# SCH_card_2024-05-29.net
KiCad netlist of a schematic drawn in EasyEDA
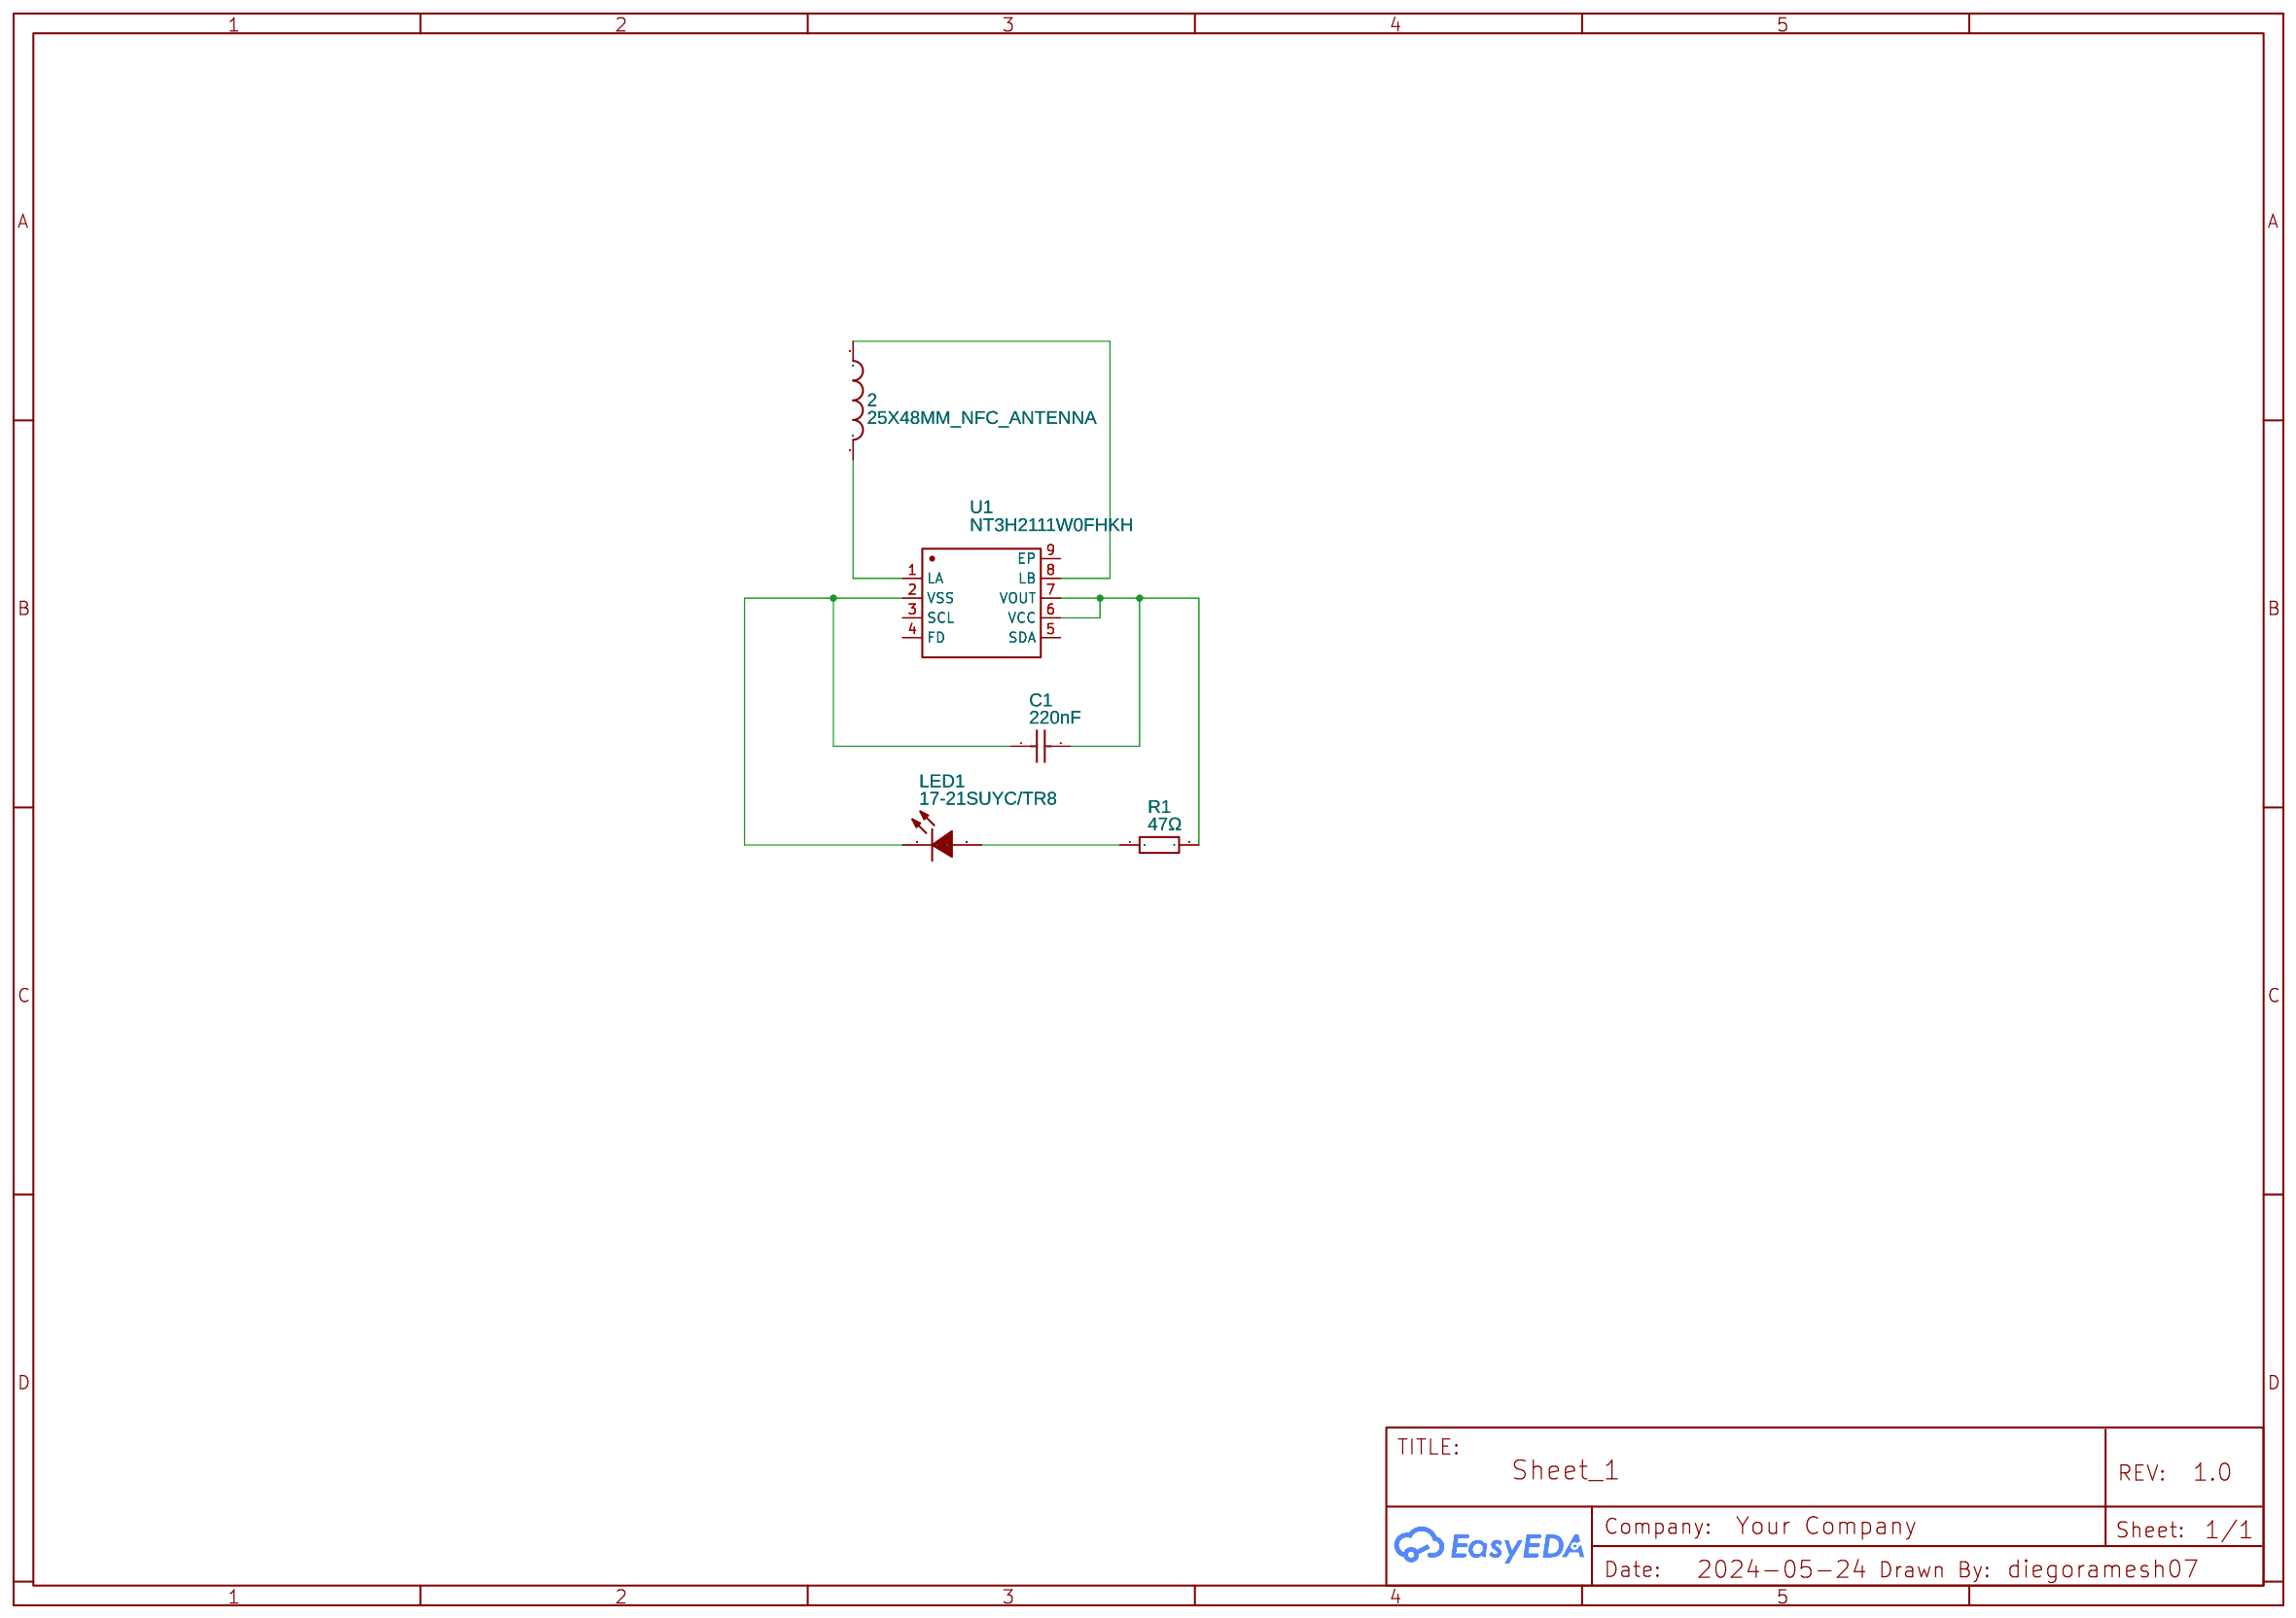
[diagram p0: schematic sheet]

(export (version "E")
  (design (tool "Eeschema 10.0.6"))
  (components
    (comp (ref "2") (value "25X48MM_NFC_ANTENNA") (libsource (lib "") (part "25X48MM_NFC_ANTENNA")))
    (comp (ref "C1")
      (value "220nF")
      (fields
        (field (name "Manufacturer Part") "CL10B224KA8NNNC")
        (field (name "Manufacturer") "SAMSUNG(三星)")
      )
      (libsource (lib "") (part "CL10B224KA8NNNC"))
    )
    (comp (ref "LED1")
      (value "17-21SUYC/TR8")
      (fields (field (name "Manufacturer Part") "KT-0805黄灯") (field (name "Manufacturer") "KENTO"))
      (libsource (lib "") (part "17-21SUYC/TR8"))
    )
    (comp (ref "R1")
      (value "47Ω")
      (fields
        (field (name "Manufacturer Part") "0603WAF470JT5E")
        (field (name "Manufacturer") "UNI-ROYAL(厚声)")
      )
      (libsource (lib "") (part "0603WAF470JT5E"))
    )
    (comp (ref "U1")
      (value "NT3H2111W0FHKH")
      (fields (field (name "Manufacturer") "NXP(恩智浦)"))
      (libsource (lib "") (part "NT3H2111W0FHKH"))
    )
  )
  (nets
    (net (code "1") (name "Net-(LED1-+)") (class "Default")
      (node (ref "LED1") (pin "1") (pinfunction "+_1") (pintype "unspecified"))
      (node (ref "R1") (pin "1") (pinfunction "1_1") (pintype "input"))
    )
    (net (code "2") (name "Net-(LED1--)") (class "Default")
      (node (ref "C1") (pin "1") (pinfunction "1_1") (pintype "input"))
      (node (ref "LED1") (pin "2") (pinfunction "-_2") (pintype "unspecified"))
      (node (ref "U1") (pin "2") (pinfunction "VSS_2") (pintype "unspecified"))
    )
    (net (code "3") (name "Net-(U1-LA)") (class "Default")
      (node (ref "2") (pin "P$2") (pinfunction "P$2_P$2") (pintype "bidirectional"))
      (node (ref "U1") (pin "1") (pinfunction "LA_1") (pintype "unspecified"))
    )
    (net (code "4") (name "Net-(U1-LB)") (class "Default")
      (node (ref "2") (pin "P$1") (pinfunction "P$1_P$1") (pintype "bidirectional"))
      (node (ref "U1") (pin "8") (pinfunction "LB_8") (pintype "unspecified"))
    )
    (net (code "5") (name "Net-(U1-VCC)") (class "Default")
      (node (ref "C1") (pin "2") (pinfunction "2_2") (pintype "input"))
      (node (ref "R1") (pin "2") (pinfunction "2_2") (pintype "input"))
      (node (ref "U1") (pin "6") (pinfunction "VCC_6") (pintype "unspecified"))
      (node (ref "U1") (pin "7") (pinfunction "VOUT_7") (pintype "unspecified"))
    )
    (net (code "6") (name "unconnected-(U1-EP-Pad9)") (class "Default")
      (node (ref "U1") (pin "9") (pinfunction "EP_9") (pintype "unspecified"))
    )
    (net (code "7") (name "unconnected-(U1-FD-Pad4)") (class "Default")
      (node (ref "U1") (pin "4") (pinfunction "FD_4") (pintype "unspecified"))
    )
    (net (code "8") (name "unconnected-(U1-SCL-Pad3)") (class "Default")
      (node (ref "U1") (pin "3") (pinfunction "SCL_3") (pintype "unspecified"))
    )
    (net (code "9") (name "unconnected-(U1-SDA-Pad5)") (class "Default")
      (node (ref "U1") (pin "5") (pinfunction "SDA_5") (pintype "unspecified"))
    )
  )
)
